# DonglePi.net
KiCad netlist of a schematic drawn in EAGLE
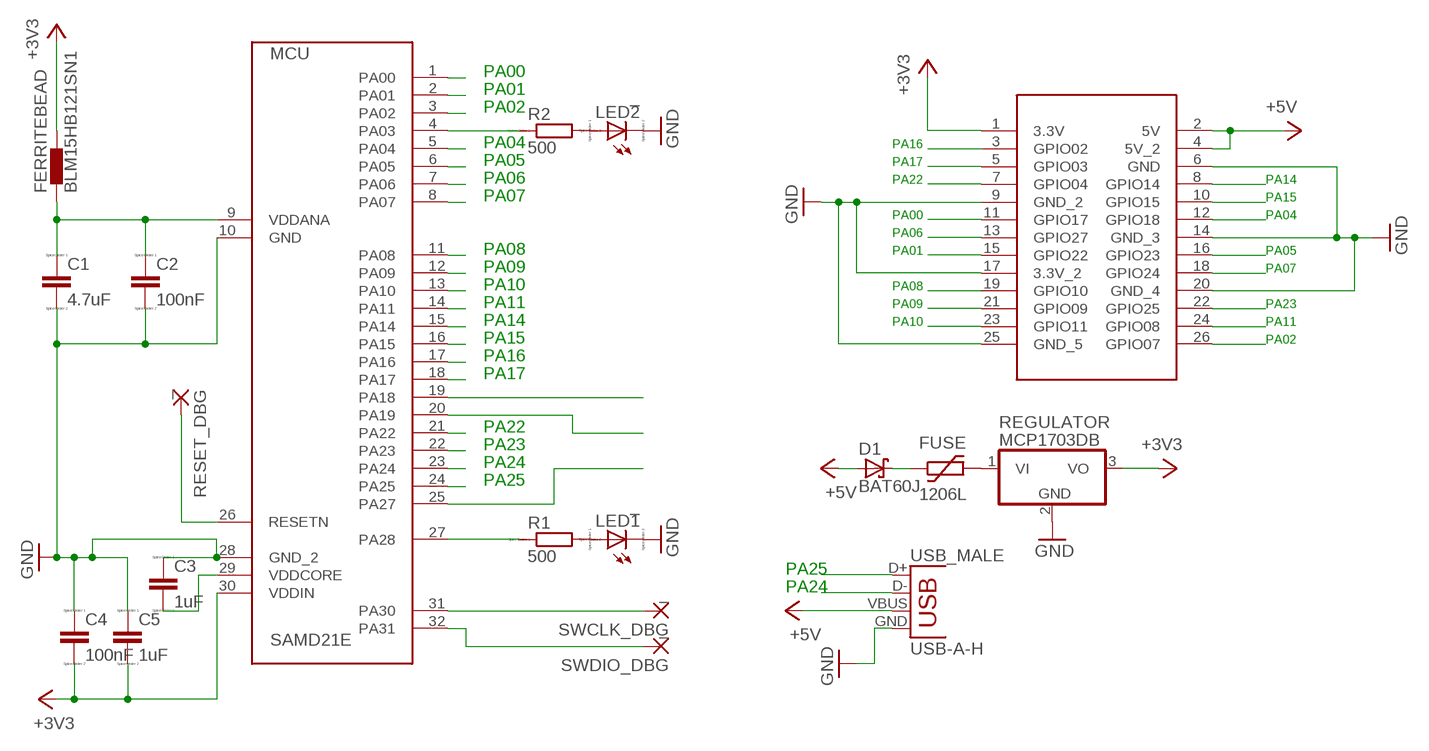
[diagram p0: schematic, sheet 1]

(export (version "E")
  (design (tool "Eeschema 10.0.6"))
  (components
    (comp (ref "C1")
      (value "4.7uF")
      (footprint "eagle-import:C0504")
      (libsource (lib "eagle-import") (part "CC0504"))
    )
    (comp (ref "C2")
      (value "100nF")
      (footprint "eagle-import:C0504")
      (libsource (lib "eagle-import") (part "CC0504"))
    )
    (comp (ref "C3")
      (value "1uF")
      (footprint "eagle-import:C0504")
      (libsource (lib "eagle-import") (part "CC0504"))
    )
    (comp (ref "C4")
      (value "100nF")
      (footprint "eagle-import:C0504")
      (libsource (lib "eagle-import") (part "CC0504"))
    )
    (comp (ref "C5")
      (value "1uF")
      (footprint "eagle-import:C0504")
      (libsource (lib "eagle-import") (part "CC0504"))
    )
    (comp (ref "D1")
      (value "BAT60J")
      (footprint "eagle-import:SOD323_ST")
      (libsource (lib "eagle-import") (part "BAT60J"))
    )
    (comp (ref "FERRITEBEAD")
      (value "BLM15HB121SN1")
      (footprint "eagle-import:0402")
      (libsource (lib "eagle-import") (part "BLM15HB121SN1"))
    )
    (comp (ref "FUSE")
      (value "1206L")
      (footprint "eagle-import:1206L")
      (libsource (lib "eagle-import") (part "1206L"))
    )
    (comp (ref "LED1")
      (value "_")
      (footprint "eagle-import:LED_SML0603")
      (libsource (lib "eagle-import") (part "LED_ESML0603"))
    )
    (comp (ref "LED2")
      (value "_")
      (footprint "eagle-import:LED_SML0603")
      (libsource (lib "eagle-import") (part "LED_ESML0603"))
    )
    (comp (ref "MCU")
      (value "SAMD21E")
      (footprint "eagle-import:TQFP32")
      (libsource (lib "eagle-import") (part "SAMD21E"))
    )
    (comp (ref "R1")
      (value "500")
      (footprint "eagle-import:R0201")
      (libsource (lib "eagle-import") (part "RR0201"))
    )
    (comp (ref "R2")
      (value "500")
      (footprint "eagle-import:R0201")
      (libsource (lib "eagle-import") (part "RR0201"))
    )
    (comp (ref "REGULATOR")
      (value "MCP1703DB")
      (footprint "eagle-import:SOT223")
      (libsource (lib "eagle-import") (part "MCP1703DB"))
    )
    (comp (ref "RESET_DBG")
      (value "_")
      (footprint "eagle-import:1,6_0,8")
      (libsource (lib "eagle-import") (part "1,6/0,8"))
    )
    (comp (ref "RPIO")
      (value "RPI_2X13")
      (footprint "eagle-import:2X13")
      (libsource (lib "eagle-import") (part "RPI_2X13"))
    )
    (comp (ref "SWCLK_DBG")
      (value "_")
      (footprint "eagle-import:1,6_0,8")
      (libsource (lib "eagle-import") (part "1,6/0,8"))
    )
    (comp (ref "SWDIO_DBG")
      (value "_")
      (footprint "eagle-import:1,6_0,8")
      (libsource (lib "eagle-import") (part "1,6/0,8"))
    )
    (comp (ref "USB_MALE")
      (value "USB-A-H")
      (footprint "eagle-import:USB-A-H")
      (libsource (lib "eagle-import") (part "USB-A-H"))
    )
  )
  (nets
    (net (code "1") (name "+3V3") (class "Default")
      (node (ref "C4") (pin "2") (pinfunction "2_2") (pintype "passive"))
      (node (ref "C5") (pin "2") (pinfunction "2_2") (pintype "passive"))
      (node (ref "FERRITEBEAD") (pin "2") (pinfunction "2_2") (pintype "passive"))
      (node (ref "MCU") (pin "30") (pinfunction "VDDIN_30") (pintype "power_in"))
      (node (ref "REGULATOR") (pin "3") (pinfunction "VO_3") (pintype "passive"))
      (node (ref "RPIO") (pin "1") (pinfunction "3.3V_1") (pintype "power_in"))
    )
    (net (code "2") (name "+5V") (class "Default")
      (node (ref "D1") (pin "A") (pinfunction "A_A") (pintype "passive"))
      (node (ref "RPIO") (pin "2") (pinfunction "5V_2") (pintype "power_in"))
      (node (ref "RPIO") (pin "4") (pinfunction "5V_2_4") (pintype "power_in"))
      (node (ref "USB_MALE") (pin "VBUS") (pinfunction "VBUS_VBUS") (pintype "bidirectional"))
    )
    (net (code "3") (name "/PA00") (class "Default")
      (node (ref "MCU") (pin "1") (pinfunction "PA00_1") (pintype "bidirectional"))
      (node (ref "RPIO") (pin "11") (pinfunction "GPIO17_11") (pintype "bidirectional"))
    )
    (net (code "4") (name "/PA01") (class "Default")
      (node (ref "MCU") (pin "2") (pinfunction "PA01_2") (pintype "bidirectional"))
      (node (ref "RPIO") (pin "15") (pinfunction "GPIO22_15") (pintype "bidirectional"))
    )
    (net (code "5") (name "/PA02") (class "Default")
      (node (ref "MCU") (pin "3") (pinfunction "PA02_3") (pintype "bidirectional"))
      (node (ref "RPIO") (pin "26") (pinfunction "GPIO07_26") (pintype "bidirectional"))
    )
    (net (code "6") (name "/PA04") (class "Default")
      (node (ref "MCU") (pin "5") (pinfunction "PA04_5") (pintype "bidirectional"))
      (node (ref "RPIO") (pin "12") (pinfunction "GPIO18_12") (pintype "bidirectional"))
    )
    (net (code "7") (name "/PA05") (class "Default")
      (node (ref "MCU") (pin "6") (pinfunction "PA05_6") (pintype "bidirectional"))
      (node (ref "RPIO") (pin "16") (pinfunction "GPIO23_16") (pintype "bidirectional"))
    )
    (net (code "8") (name "/PA06") (class "Default")
      (node (ref "MCU") (pin "7") (pinfunction "PA06_7") (pintype "bidirectional"))
      (node (ref "RPIO") (pin "13") (pinfunction "GPIO27_13") (pintype "bidirectional"))
    )
    (net (code "9") (name "/PA07") (class "Default")
      (node (ref "MCU") (pin "8") (pinfunction "PA07_8") (pintype "bidirectional"))
      (node (ref "RPIO") (pin "18") (pinfunction "GPIO24_18") (pintype "bidirectional"))
    )
    (net (code "10") (name "/PA08") (class "Default")
      (node (ref "MCU") (pin "11") (pinfunction "PA08_11") (pintype "bidirectional"))
      (node (ref "RPIO") (pin "19") (pinfunction "GPIO10_19") (pintype "bidirectional"))
    )
    (net (code "11") (name "/PA09") (class "Default")
      (node (ref "MCU") (pin "12") (pinfunction "PA09_12") (pintype "bidirectional"))
      (node (ref "RPIO") (pin "21") (pinfunction "GPIO09_21") (pintype "bidirectional"))
    )
    (net (code "12") (name "/PA10") (class "Default")
      (node (ref "MCU") (pin "13") (pinfunction "PA10_13") (pintype "bidirectional"))
      (node (ref "RPIO") (pin "23") (pinfunction "GPIO11_23") (pintype "bidirectional"))
    )
    (net (code "13") (name "/PA11") (class "Default")
      (node (ref "MCU") (pin "14") (pinfunction "PA11_14") (pintype "bidirectional"))
      (node (ref "RPIO") (pin "24") (pinfunction "GPIO08_24") (pintype "bidirectional"))
    )
    (net (code "14") (name "/PA14") (class "Default")
      (node (ref "MCU") (pin "15") (pinfunction "PA14_15") (pintype "bidirectional"))
      (node (ref "RPIO") (pin "8") (pinfunction "GPIO14_8") (pintype "bidirectional"))
    )
    (net (code "15") (name "/PA15") (class "Default")
      (node (ref "MCU") (pin "16") (pinfunction "PA15_16") (pintype "bidirectional"))
      (node (ref "RPIO") (pin "10") (pinfunction "GPIO15_10") (pintype "bidirectional"))
    )
    (net (code "16") (name "/PA16") (class "Default")
      (node (ref "MCU") (pin "17") (pinfunction "PA16_17") (pintype "bidirectional"))
      (node (ref "RPIO") (pin "3") (pinfunction "GPIO02_3") (pintype "bidirectional"))
    )
    (net (code "17") (name "/PA17") (class "Default")
      (node (ref "MCU") (pin "18") (pinfunction "PA17_18") (pintype "bidirectional"))
      (node (ref "RPIO") (pin "5") (pinfunction "GPIO03_5") (pintype "bidirectional"))
    )
    (net (code "18") (name "/PA22") (class "Default")
      (node (ref "MCU") (pin "21") (pinfunction "PA22_21") (pintype "bidirectional"))
      (node (ref "RPIO") (pin "7") (pinfunction "GPIO04_7") (pintype "bidirectional"))
    )
    (net (code "19") (name "/PA23") (class "Default")
      (node (ref "MCU") (pin "22") (pinfunction "PA23_22") (pintype "bidirectional"))
      (node (ref "RPIO") (pin "22") (pinfunction "GPIO25_22") (pintype "bidirectional"))
    )
    (net (code "20") (name "/PA24") (class "Default")
      (node (ref "MCU") (pin "23") (pinfunction "PA24_23") (pintype "bidirectional"))
      (node (ref "USB_MALE") (pin "D-") (pinfunction "D-_D-") (pintype "bidirectional"))
    )
    (net (code "21") (name "/PA25") (class "Default")
      (node (ref "MCU") (pin "24") (pinfunction "PA25_24") (pintype "bidirectional"))
      (node (ref "USB_MALE") (pin "D+") (pinfunction "D+_D+") (pintype "bidirectional"))
    )
    (net (code "22") (name "GND") (class "Default")
      (node (ref "C1") (pin "2") (pinfunction "2_2") (pintype "passive"))
      (node (ref "C2") (pin "2") (pinfunction "2_2") (pintype "passive"))
      (node (ref "C3") (pin "1") (pinfunction "1_1") (pintype "passive"))
      (node (ref "C4") (pin "1") (pinfunction "1_1") (pintype "passive"))
      (node (ref "C5") (pin "1") (pinfunction "1_1") (pintype "passive"))
      (node (ref "LED1") (pin "C") (pinfunction "C_C") (pintype "passive"))
      (node (ref "LED2") (pin "C") (pinfunction "C_C") (pintype "passive"))
      (node (ref "MCU") (pin "10") (pinfunction "GND_10") (pintype "power_in"))
      (node (ref "MCU") (pin "28") (pinfunction "GND_2_28") (pintype "power_in"))
      (node (ref "REGULATOR") (pin "2") (pinfunction "GND_2") (pintype "passive"))
      (node (ref "RPIO") (pin "14") (pinfunction "GND_3_14") (pintype "power_in"))
      (node (ref "RPIO") (pin "17") (pinfunction "3.3V_2_17") (pintype "power_in"))
      (node (ref "RPIO") (pin "20") (pinfunction "GND_4_20") (pintype "power_in"))
      (node (ref "RPIO") (pin "25") (pinfunction "GND_5_25") (pintype "power_in"))
      (node (ref "RPIO") (pin "6") (pinfunction "GND_6") (pintype "power_in"))
      (node (ref "RPIO") (pin "9") (pinfunction "GND_2_9") (pintype "power_in"))
      (node (ref "USB_MALE") (pin "GND") (pinfunction "GND_GND") (pintype "bidirectional"))
    )
    (net (code "23") (name "Net-(FUSE-1)") (class "Default")
      (node (ref "D1") (pin "C") (pinfunction "C_C") (pintype "passive"))
      (node (ref "FUSE") (pin "P$1") (pinfunction "1_P$1") (pintype "passive"))
    )
    (net (code "24") (name "Net-(FUSE-2)") (class "Default")
      (node (ref "FUSE") (pin "P$2") (pinfunction "2_P$2") (pintype "passive"))
      (node (ref "REGULATOR") (pin "1") (pinfunction "VI_1") (pintype "input"))
    )
    (net (code "25") (name "Net-(LED1-PadA)") (class "Default")
      (node (ref "LED1") (pin "A") (pinfunction "A_A") (pintype "passive"))
      (node (ref "R1") (pin "2") (pinfunction "2_2") (pintype "passive"))
    )
    (net (code "26") (name "Net-(LED2-PadA)") (class "Default")
      (node (ref "LED2") (pin "A") (pinfunction "A_A") (pintype "passive"))
      (node (ref "R2") (pin "2") (pinfunction "2_2") (pintype "passive"))
    )
    (net (code "27") (name "Net-(MCU-PA03)") (class "Default")
      (node (ref "MCU") (pin "4") (pinfunction "PA03_4") (pintype "bidirectional"))
      (node (ref "R2") (pin "1") (pinfunction "1_1") (pintype "passive"))
    )
    (net (code "28") (name "Net-(MCU-PA28)") (class "Default")
      (node (ref "MCU") (pin "27") (pinfunction "PA28_27") (pintype "bidirectional"))
      (node (ref "R1") (pin "1") (pinfunction "1_1") (pintype "passive"))
    )
    (net (code "29") (name "Net-(MCU-PA30)") (class "Default")
      (node (ref "MCU") (pin "31") (pinfunction "PA30_31") (pintype "bidirectional"))
      (node (ref "SWCLK_DBG") (pin "1") (pinfunction "P_1") (pintype "passive"))
    )
    (net (code "30") (name "Net-(MCU-PA31)") (class "Default")
      (node (ref "MCU") (pin "32") (pinfunction "PA31_32") (pintype "bidirectional"))
      (node (ref "SWDIO_DBG") (pin "1") (pinfunction "P_1") (pintype "passive"))
    )
    (net (code "31") (name "Net-(MCU-RESETN)") (class "Default")
      (node (ref "MCU") (pin "26") (pinfunction "RESETN_26") (pintype "input"))
      (node (ref "RESET_DBG") (pin "1") (pinfunction "P_1") (pintype "passive"))
    )
    (net (code "32") (name "Net-(MCU-VDDANA)") (class "Default")
      (node (ref "C1") (pin "1") (pinfunction "1_1") (pintype "passive"))
      (node (ref "C2") (pin "1") (pinfunction "1_1") (pintype "passive"))
      (node (ref "FERRITEBEAD") (pin "1") (pinfunction "1_1") (pintype "passive"))
      (node (ref "MCU") (pin "9") (pinfunction "VDDANA_9") (pintype "power_in"))
    )
    (net (code "33") (name "Net-(MCU-VDDCORE)") (class "Default")
      (node (ref "C3") (pin "2") (pinfunction "2_2") (pintype "passive"))
      (node (ref "MCU") (pin "29") (pinfunction "VDDCORE_29") (pintype "power_in"))
    )
    (net (code "34") (name "unconnected-(MCU-PA18-Pad19)") (class "Default")
      (node (ref "MCU") (pin "19") (pinfunction "PA18_19") (pintype "bidirectional"))
    )
    (net (code "35") (name "unconnected-(MCU-PA19-Pad20)") (class "Default")
      (node (ref "MCU") (pin "20") (pinfunction "PA19_20") (pintype "bidirectional"))
    )
    (net (code "36") (name "unconnected-(MCU-PA27-Pad25)") (class "Default")
      (node (ref "MCU") (pin "25") (pinfunction "PA27_25") (pintype "bidirectional"))
    )
  )
)
